# ARDUINO_MEGA2560_EXPANSION_BOARD.net
KiCad netlist of a schematic drawn in Altium Designer
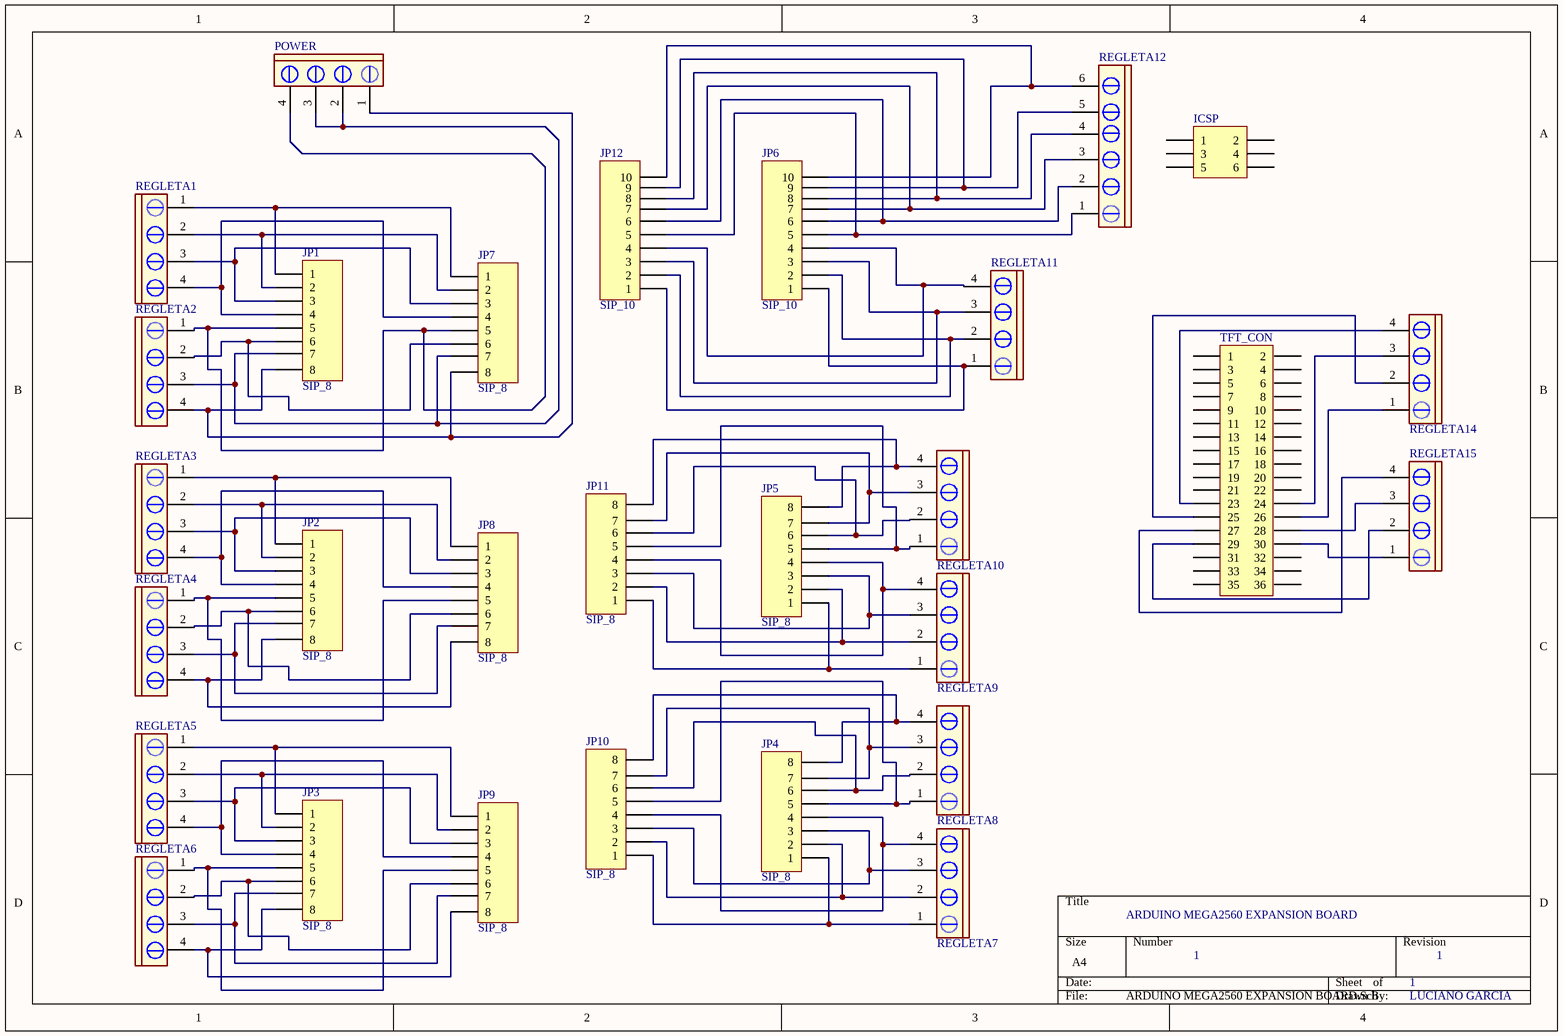
[diagram p0: ARDUINO MEGA2560 EXPANSION BOARD.SchDoc]

(export (version "E")
  (design (tool "Eeschema 10.0.6"))
  (components
    (comp (ref "ICSP")
      (value "SIP_2X3")
      (footprint "SIP_2X03")
      (libsource (lib "COMPONENTES") (part "SIP_2X3"))
    )
    (comp (ref "JP1") (value "SIP_8") (footprint "SIP_8") (libsource (lib "COMPONENTES") (part "SIP_8")))
    (comp (ref "JP2") (value "SIP_8") (footprint "SIP_8") (libsource (lib "COMPONENTES") (part "SIP_8")))
    (comp (ref "JP3") (value "SIP_8") (footprint "SIP_8") (libsource (lib "COMPONENTES") (part "SIP_8")))
    (comp (ref "JP4") (value "SIP_8") (footprint "SIP_8") (libsource (lib "") (part "SIP_8_1")))
    (comp (ref "JP5") (value "SIP_8") (footprint "SIP_8") (libsource (lib "") (part "SIP_8_1")))
    (comp (ref "JP6") (value "SIP_10") (footprint "SIP_10") (libsource (lib "COMPONENTES") (part "SIP_10")))
    (comp (ref "JP7") (value "SIP_8") (footprint "SIP_8") (libsource (lib "COMPONENTES") (part "SIP_8")))
    (comp (ref "JP8") (value "SIP_8") (footprint "SIP_8") (libsource (lib "COMPONENTES") (part "SIP_8")))
    (comp (ref "JP9") (value "SIP_8") (footprint "SIP_8") (libsource (lib "COMPONENTES") (part "SIP_8")))
    (comp (ref "JP10") (value "SIP_8") (footprint "SIP_8") (libsource (lib "") (part "SIP_8_1")))
    (comp (ref "JP11") (value "SIP_8") (footprint "SIP_8") (libsource (lib "") (part "SIP_8_1")))
    (comp (ref "JP12") (value "SIP_10") (footprint "SIP_10") (libsource (lib "COMPONENTES") (part "SIP_10")))
    (comp (ref "POWER") (value "REGLETA_4") (footprint "REGLETA_4") (libsource (lib "") (part "REGLETA_4_2")))
    (comp (ref "REGLETA1")
      (value "REGLETA_4")
      (footprint "REGLETA_4")
      (libsource (lib "COMPONENTES") (part "REGLETA_4"))
    )
    (comp (ref "REGLETA2")
      (value "REGLETA_4")
      (footprint "REGLETA_4")
      (libsource (lib "COMPONENTES") (part "REGLETA_4"))
    )
    (comp (ref "REGLETA3")
      (value "REGLETA_4")
      (footprint "REGLETA_4")
      (libsource (lib "COMPONENTES") (part "REGLETA_4"))
    )
    (comp (ref "REGLETA4")
      (value "REGLETA_4")
      (footprint "REGLETA_4")
      (libsource (lib "COMPONENTES") (part "REGLETA_4"))
    )
    (comp (ref "REGLETA5")
      (value "REGLETA_4")
      (footprint "REGLETA_4")
      (libsource (lib "COMPONENTES") (part "REGLETA_4"))
    )
    (comp (ref "REGLETA6")
      (value "REGLETA_4")
      (footprint "REGLETA_4")
      (libsource (lib "COMPONENTES") (part "REGLETA_4"))
    )
    (comp (ref "REGLETA7")
      (value "REGLETA_4")
      (footprint "REGLETA_4")
      (libsource (lib "") (part "REGLETA_4_1"))
    )
    (comp (ref "REGLETA8")
      (value "REGLETA_4")
      (footprint "REGLETA_4")
      (libsource (lib "") (part "REGLETA_4_1"))
    )
    (comp (ref "REGLETA9")
      (value "REGLETA_4")
      (footprint "REGLETA_4")
      (libsource (lib "") (part "REGLETA_4_1"))
    )
    (comp (ref "REGLETA10")
      (value "REGLETA_4")
      (footprint "REGLETA_4")
      (libsource (lib "") (part "REGLETA_4_1"))
    )
    (comp (ref "REGLETA11")
      (value "REGLETA_4")
      (footprint "REGLETA_4")
      (libsource (lib "") (part "REGLETA_4_1"))
    )
    (comp (ref "REGLETA12")
      (value "REGLETA_6")
      (footprint "REGLETA_6")
      (libsource (lib "COMPONENTES") (part "REGLETA_6"))
    )
    (comp (ref "REGLETA14")
      (value "REGLETA_4")
      (footprint "REGLETA_4")
      (libsource (lib "") (part "REGLETA_4_1"))
    )
    (comp (ref "REGLETA15")
      (value "REGLETA_4")
      (footprint "REGLETA_4")
      (libsource (lib "") (part "REGLETA_4_1"))
    )
    (comp (ref "TFT_CON")
      (value "SIP_2X18")
      (footprint "SIP_2X18")
      (libsource (lib "COMPONENTES") (part "SIP_2X18"))
    )
  )
  (nets
    (net (code "1") (name "Net-(JP1-Pad1)") (class "Default")
      (node (ref "JP1") (pin "1") (pinfunction "1_1") (pintype "passive"))
      (node (ref "JP7") (pin "1") (pinfunction "1_1") (pintype "passive"))
      (node (ref "REGLETA1") (pin "1") (pinfunction "1_1") (pintype "passive"))
    )
    (net (code "2") (name "Net-(JP1-Pad2)") (class "Default")
      (node (ref "JP1") (pin "2") (pinfunction "2_2") (pintype "passive"))
      (node (ref "JP7") (pin "2") (pinfunction "2_2") (pintype "passive"))
      (node (ref "REGLETA1") (pin "2") (pinfunction "2_2") (pintype "passive"))
    )
    (net (code "3") (name "Net-(JP1-Pad3)") (class "Default")
      (node (ref "JP1") (pin "3") (pinfunction "3_3") (pintype "passive"))
      (node (ref "JP7") (pin "3") (pinfunction "3_3") (pintype "passive"))
      (node (ref "REGLETA1") (pin "3") (pinfunction "3_3") (pintype "passive"))
    )
    (net (code "4") (name "Net-(JP1-Pad4)") (class "Default")
      (node (ref "JP1") (pin "4") (pinfunction "4_4") (pintype "passive"))
      (node (ref "JP7") (pin "4") (pinfunction "4_4") (pintype "passive"))
      (node (ref "REGLETA1") (pin "4") (pinfunction "4_4") (pintype "passive"))
    )
    (net (code "5") (name "Net-(JP1-Pad5)") (class "Default")
      (node (ref "JP1") (pin "5") (pinfunction "5_5") (pintype "passive"))
      (node (ref "JP7") (pin "5") (pinfunction "5_5") (pintype "passive"))
      (node (ref "POWER") (pin "4") (pinfunction "4_4") (pintype "passive"))
      (node (ref "REGLETA2") (pin "1") (pinfunction "1_1") (pintype "passive"))
    )
    (net (code "6") (name "Net-(JP1-Pad6)") (class "Default")
      (node (ref "JP1") (pin "6") (pinfunction "6_6") (pintype "passive"))
      (node (ref "JP7") (pin "6") (pinfunction "6_6") (pintype "passive"))
      (node (ref "REGLETA2") (pin "2") (pinfunction "2_2") (pintype "passive"))
    )
    (net (code "7") (name "Net-(JP1-Pad7)") (class "Default")
      (node (ref "JP1") (pin "7") (pinfunction "7_7") (pintype "passive"))
      (node (ref "JP7") (pin "7") (pinfunction "7_7") (pintype "passive"))
      (node (ref "POWER") (pin "2") (pinfunction "2_2") (pintype "passive"))
      (node (ref "POWER") (pin "3") (pinfunction "3_3") (pintype "passive"))
      (node (ref "REGLETA2") (pin "3") (pinfunction "3_3") (pintype "passive"))
    )
    (net (code "8") (name "Net-(JP1-Pad8)") (class "Default")
      (node (ref "JP1") (pin "8") (pinfunction "8_8") (pintype "passive"))
      (node (ref "JP7") (pin "8") (pinfunction "8_8") (pintype "passive"))
      (node (ref "POWER") (pin "1") (pinfunction "1_1") (pintype "passive"))
      (node (ref "REGLETA2") (pin "4") (pinfunction "4_4") (pintype "passive"))
    )
    (net (code "9") (name "Net-(JP2-Pad1)") (class "Default")
      (node (ref "JP2") (pin "1") (pinfunction "1_1") (pintype "passive"))
      (node (ref "JP8") (pin "1") (pinfunction "1_1") (pintype "passive"))
      (node (ref "REGLETA3") (pin "1") (pinfunction "1_1") (pintype "passive"))
    )
    (net (code "10") (name "Net-(JP2-Pad2)") (class "Default")
      (node (ref "JP2") (pin "2") (pinfunction "2_2") (pintype "passive"))
      (node (ref "JP8") (pin "2") (pinfunction "2_2") (pintype "passive"))
      (node (ref "REGLETA3") (pin "2") (pinfunction "2_2") (pintype "passive"))
    )
    (net (code "11") (name "Net-(JP2-Pad3)") (class "Default")
      (node (ref "JP2") (pin "3") (pinfunction "3_3") (pintype "passive"))
      (node (ref "JP8") (pin "3") (pinfunction "3_3") (pintype "passive"))
      (node (ref "REGLETA3") (pin "3") (pinfunction "3_3") (pintype "passive"))
    )
    (net (code "12") (name "Net-(JP2-Pad4)") (class "Default")
      (node (ref "JP2") (pin "4") (pinfunction "4_4") (pintype "passive"))
      (node (ref "JP8") (pin "4") (pinfunction "4_4") (pintype "passive"))
      (node (ref "REGLETA3") (pin "4") (pinfunction "4_4") (pintype "passive"))
    )
    (net (code "13") (name "Net-(JP2-Pad5)") (class "Default")
      (node (ref "JP2") (pin "5") (pinfunction "5_5") (pintype "passive"))
      (node (ref "JP8") (pin "5") (pinfunction "5_5") (pintype "passive"))
      (node (ref "REGLETA4") (pin "1") (pinfunction "1_1") (pintype "passive"))
    )
    (net (code "14") (name "Net-(JP2-Pad6)") (class "Default")
      (node (ref "JP2") (pin "6") (pinfunction "6_6") (pintype "passive"))
      (node (ref "JP8") (pin "6") (pinfunction "6_6") (pintype "passive"))
      (node (ref "REGLETA4") (pin "2") (pinfunction "2_2") (pintype "passive"))
    )
    (net (code "15") (name "Net-(JP2-Pad7)") (class "Default")
      (node (ref "JP2") (pin "7") (pinfunction "7_7") (pintype "passive"))
      (node (ref "JP8") (pin "7") (pinfunction "7_7") (pintype "passive"))
      (node (ref "REGLETA4") (pin "3") (pinfunction "3_3") (pintype "passive"))
    )
    (net (code "16") (name "Net-(JP2-Pad8)") (class "Default")
      (node (ref "JP2") (pin "8") (pinfunction "8_8") (pintype "passive"))
      (node (ref "JP8") (pin "8") (pinfunction "8_8") (pintype "passive"))
      (node (ref "REGLETA4") (pin "4") (pinfunction "4_4") (pintype "passive"))
    )
    (net (code "17") (name "Net-(JP3-Pad1)") (class "Default")
      (node (ref "JP3") (pin "1") (pinfunction "1_1") (pintype "passive"))
      (node (ref "JP9") (pin "1") (pinfunction "1_1") (pintype "passive"))
      (node (ref "REGLETA5") (pin "1") (pinfunction "1_1") (pintype "passive"))
    )
    (net (code "18") (name "Net-(JP3-Pad2)") (class "Default")
      (node (ref "JP3") (pin "2") (pinfunction "2_2") (pintype "passive"))
      (node (ref "JP9") (pin "2") (pinfunction "2_2") (pintype "passive"))
      (node (ref "REGLETA5") (pin "2") (pinfunction "2_2") (pintype "passive"))
    )
    (net (code "19") (name "Net-(JP3-Pad3)") (class "Default")
      (node (ref "JP3") (pin "3") (pinfunction "3_3") (pintype "passive"))
      (node (ref "JP9") (pin "3") (pinfunction "3_3") (pintype "passive"))
      (node (ref "REGLETA5") (pin "3") (pinfunction "3_3") (pintype "passive"))
    )
    (net (code "20") (name "Net-(JP3-Pad4)") (class "Default")
      (node (ref "JP3") (pin "4") (pinfunction "4_4") (pintype "passive"))
      (node (ref "JP9") (pin "4") (pinfunction "4_4") (pintype "passive"))
      (node (ref "REGLETA5") (pin "4") (pinfunction "4_4") (pintype "passive"))
    )
    (net (code "21") (name "Net-(JP3-Pad5)") (class "Default")
      (node (ref "JP3") (pin "5") (pinfunction "5_5") (pintype "passive"))
      (node (ref "JP9") (pin "5") (pinfunction "5_5") (pintype "passive"))
      (node (ref "REGLETA6") (pin "1") (pinfunction "1_1") (pintype "passive"))
    )
    (net (code "22") (name "Net-(JP3-Pad6)") (class "Default")
      (node (ref "JP3") (pin "6") (pinfunction "6_6") (pintype "passive"))
      (node (ref "JP9") (pin "6") (pinfunction "6_6") (pintype "passive"))
      (node (ref "REGLETA6") (pin "2") (pinfunction "2_2") (pintype "passive"))
    )
    (net (code "23") (name "Net-(JP3-Pad7)") (class "Default")
      (node (ref "JP3") (pin "7") (pinfunction "7_7") (pintype "passive"))
      (node (ref "JP9") (pin "7") (pinfunction "7_7") (pintype "passive"))
      (node (ref "REGLETA6") (pin "3") (pinfunction "3_3") (pintype "passive"))
    )
    (net (code "24") (name "Net-(JP3-Pad8)") (class "Default")
      (node (ref "JP3") (pin "8") (pinfunction "8_8") (pintype "passive"))
      (node (ref "JP9") (pin "8") (pinfunction "8_8") (pintype "passive"))
      (node (ref "REGLETA6") (pin "4") (pinfunction "4_4") (pintype "passive"))
    )
    (net (code "25") (name "Net-(JP10-Pad1)") (class "Default")
      (node (ref "JP10") (pin "1") (pinfunction "1_1") (pintype "passive"))
      (node (ref "JP4") (pin "1") (pinfunction "1_1") (pintype "passive"))
      (node (ref "REGLETA7") (pin "1") (pinfunction "1_1") (pintype "passive"))
    )
    (net (code "26") (name "Net-(JP10-Pad2)") (class "Default")
      (node (ref "JP10") (pin "2") (pinfunction "2_2") (pintype "passive"))
      (node (ref "JP4") (pin "2") (pinfunction "2_2") (pintype "passive"))
      (node (ref "REGLETA7") (pin "2") (pinfunction "2_2") (pintype "passive"))
    )
    (net (code "27") (name "Net-(JP10-Pad3)") (class "Default")
      (node (ref "JP10") (pin "3") (pinfunction "3_3") (pintype "passive"))
      (node (ref "JP4") (pin "3") (pinfunction "3_3") (pintype "passive"))
      (node (ref "REGLETA7") (pin "3") (pinfunction "3_3") (pintype "passive"))
    )
    (net (code "28") (name "Net-(JP10-Pad4)") (class "Default")
      (node (ref "JP10") (pin "4") (pinfunction "4_4") (pintype "passive"))
      (node (ref "JP4") (pin "4") (pinfunction "4_4") (pintype "passive"))
      (node (ref "REGLETA7") (pin "4") (pinfunction "4_4") (pintype "passive"))
    )
    (net (code "29") (name "Net-(JP10-Pad5)") (class "Default")
      (node (ref "JP10") (pin "5") (pinfunction "5_5") (pintype "passive"))
      (node (ref "JP4") (pin "5") (pinfunction "5_5") (pintype "passive"))
      (node (ref "REGLETA8") (pin "1") (pinfunction "1_1") (pintype "passive"))
    )
    (net (code "30") (name "Net-(JP10-Pad6)") (class "Default")
      (node (ref "JP10") (pin "6") (pinfunction "6_6") (pintype "passive"))
      (node (ref "JP4") (pin "6") (pinfunction "6_6") (pintype "passive"))
      (node (ref "REGLETA8") (pin "2") (pinfunction "2_2") (pintype "passive"))
    )
    (net (code "31") (name "Net-(JP10-Pad7)") (class "Default")
      (node (ref "JP10") (pin "7") (pinfunction "7_7") (pintype "passive"))
      (node (ref "JP4") (pin "7") (pinfunction "7_7") (pintype "passive"))
      (node (ref "REGLETA8") (pin "3") (pinfunction "3_3") (pintype "passive"))
    )
    (net (code "32") (name "Net-(JP10-Pad8)") (class "Default")
      (node (ref "JP10") (pin "8") (pinfunction "8_8") (pintype "passive"))
      (node (ref "JP4") (pin "8") (pinfunction "8_8") (pintype "passive"))
      (node (ref "REGLETA8") (pin "4") (pinfunction "4_4") (pintype "passive"))
    )
    (net (code "33") (name "Net-(JP11-Pad1)") (class "Default")
      (node (ref "JP11") (pin "1") (pinfunction "1_1") (pintype "passive"))
      (node (ref "JP5") (pin "1") (pinfunction "1_1") (pintype "passive"))
      (node (ref "REGLETA9") (pin "1") (pinfunction "1_1") (pintype "passive"))
    )
    (net (code "34") (name "Net-(JP11-Pad2)") (class "Default")
      (node (ref "JP11") (pin "2") (pinfunction "2_2") (pintype "passive"))
      (node (ref "JP5") (pin "2") (pinfunction "2_2") (pintype "passive"))
      (node (ref "REGLETA9") (pin "2") (pinfunction "2_2") (pintype "passive"))
    )
    (net (code "35") (name "Net-(JP11-Pad3)") (class "Default")
      (node (ref "JP11") (pin "3") (pinfunction "3_3") (pintype "passive"))
      (node (ref "JP5") (pin "3") (pinfunction "3_3") (pintype "passive"))
      (node (ref "REGLETA9") (pin "3") (pinfunction "3_3") (pintype "passive"))
    )
    (net (code "36") (name "Net-(JP11-Pad4)") (class "Default")
      (node (ref "JP11") (pin "4") (pinfunction "4_4") (pintype "passive"))
      (node (ref "JP5") (pin "4") (pinfunction "4_4") (pintype "passive"))
      (node (ref "REGLETA9") (pin "4") (pinfunction "4_4") (pintype "passive"))
    )
    (net (code "37") (name "Net-(JP11-Pad5)") (class "Default")
      (node (ref "JP11") (pin "5") (pinfunction "5_5") (pintype "passive"))
      (node (ref "JP5") (pin "5") (pinfunction "5_5") (pintype "passive"))
      (node (ref "REGLETA10") (pin "1") (pinfunction "1_1") (pintype "passive"))
    )
    (net (code "38") (name "Net-(JP11-Pad6)") (class "Default")
      (node (ref "JP11") (pin "6") (pinfunction "6_6") (pintype "passive"))
      (node (ref "JP5") (pin "6") (pinfunction "6_6") (pintype "passive"))
      (node (ref "REGLETA10") (pin "2") (pinfunction "2_2") (pintype "passive"))
    )
    (net (code "39") (name "Net-(JP11-Pad7)") (class "Default")
      (node (ref "JP11") (pin "7") (pinfunction "7_7") (pintype "passive"))
      (node (ref "JP5") (pin "7") (pinfunction "7_7") (pintype "passive"))
      (node (ref "REGLETA10") (pin "3") (pinfunction "3_3") (pintype "passive"))
    )
    (net (code "40") (name "Net-(JP11-Pad8)") (class "Default")
      (node (ref "JP11") (pin "8") (pinfunction "8_8") (pintype "passive"))
      (node (ref "JP5") (pin "8") (pinfunction "8_8") (pintype "passive"))
      (node (ref "REGLETA10") (pin "4") (pinfunction "4_4") (pintype "passive"))
    )
    (net (code "41") (name "Net-(JP12-Pad1)") (class "Default")
      (node (ref "JP12") (pin "1") (pinfunction "1_1") (pintype "passive"))
      (node (ref "JP6") (pin "1") (pinfunction "1_1") (pintype "passive"))
      (node (ref "REGLETA11") (pin "1") (pinfunction "1_1") (pintype "passive"))
    )
    (net (code "42") (name "Net-(JP12-Pad2)") (class "Default")
      (node (ref "JP12") (pin "2") (pinfunction "2_2") (pintype "passive"))
      (node (ref "JP6") (pin "2") (pinfunction "2_2") (pintype "passive"))
      (node (ref "REGLETA11") (pin "2") (pinfunction "2_2") (pintype "passive"))
    )
    (net (code "43") (name "Net-(JP12-Pad3)") (class "Default")
      (node (ref "JP12") (pin "3") (pinfunction "3_3") (pintype "passive"))
      (node (ref "JP6") (pin "3") (pinfunction "3_3") (pintype "passive"))
      (node (ref "REGLETA11") (pin "3") (pinfunction "3_3") (pintype "passive"))
    )
    (net (code "44") (name "Net-(JP12-Pad4)") (class "Default")
      (node (ref "JP12") (pin "4") (pinfunction "4_4") (pintype "passive"))
      (node (ref "JP6") (pin "4") (pinfunction "4_4") (pintype "passive"))
      (node (ref "REGLETA11") (pin "4") (pinfunction "4_4") (pintype "passive"))
    )
    (net (code "45") (name "Net-(JP12-Pad5)") (class "Default")
      (node (ref "JP12") (pin "5") (pinfunction "5_5") (pintype "passive"))
      (node (ref "JP6") (pin "5") (pinfunction "5_5") (pintype "passive"))
      (node (ref "REGLETA12") (pin "1") (pinfunction "1_1") (pintype "passive"))
    )
    (net (code "46") (name "Net-(JP12-Pad6)") (class "Default")
      (node (ref "JP12") (pin "6") (pinfunction "6_6") (pintype "passive"))
      (node (ref "JP6") (pin "6") (pinfunction "6_6") (pintype "passive"))
      (node (ref "REGLETA12") (pin "2") (pinfunction "2_2") (pintype "passive"))
    )
    (net (code "47") (name "Net-(JP12-Pad7)") (class "Default")
      (node (ref "JP12") (pin "7") (pinfunction "7_7") (pintype "passive"))
      (node (ref "JP6") (pin "7") (pinfunction "7_7") (pintype "passive"))
      (node (ref "REGLETA12") (pin "3") (pinfunction "3_3") (pintype "passive"))
    )
    (net (code "48") (name "Net-(JP12-Pad8)") (class "Default")
      (node (ref "JP12") (pin "8") (pinfunction "8_8") (pintype "passive"))
      (node (ref "JP6") (pin "8") (pinfunction "8_8") (pintype "passive"))
      (node (ref "REGLETA12") (pin "4") (pinfunction "4_4") (pintype "passive"))
    )
    (net (code "49") (name "Net-(JP12-Pad9)") (class "Default")
      (node (ref "JP12") (pin "9") (pinfunction "9_9") (pintype "passive"))
      (node (ref "JP6") (pin "9") (pinfunction "9_9") (pintype "passive"))
      (node (ref "REGLETA12") (pin "5") (pinfunction "5_5") (pintype "passive"))
    )
    (net (code "50") (name "Net-(JP12-Pad10)") (class "Default")
      (node (ref "JP12") (pin "10") (pinfunction "10_10") (pintype "passive"))
      (node (ref "JP6") (pin "10") (pinfunction "10_10") (pintype "passive"))
      (node (ref "REGLETA12") (pin "6") (pinfunction "6_6") (pintype "passive"))
    )
    (net (code "51") (name "Net-(REGLETA14-Pad1)") (class "Default")
      (node (ref "REGLETA14") (pin "1") (pinfunction "1_1") (pintype "passive"))
      (node (ref "TFT_CON") (pin "26") (pinfunction "26_26") (pintype "passive"))
    )
    (net (code "52") (name "Net-(REGLETA14-Pad2)") (class "Default")
      (node (ref "REGLETA14") (pin "2") (pinfunction "2_2") (pintype "passive"))
      (node (ref "TFT_CON") (pin "25") (pinfunction "25_25") (pintype "passive"))
    )
    (net (code "53") (name "Net-(REGLETA14-Pad3)") (class "Default")
      (node (ref "REGLETA14") (pin "3") (pinfunction "3_3") (pintype "passive"))
      (node (ref "TFT_CON") (pin "24") (pinfunction "24_24") (pintype "passive"))
    )
    (net (code "54") (name "Net-(REGLETA14-Pad4)") (class "Default")
      (node (ref "REGLETA14") (pin "4") (pinfunction "4_4") (pintype "passive"))
      (node (ref "TFT_CON") (pin "23") (pinfunction "23_23") (pintype "passive"))
    )
    (net (code "55") (name "Net-(REGLETA15-Pad1)") (class "Default")
      (node (ref "REGLETA15") (pin "1") (pinfunction "1_1") (pintype "passive"))
      (node (ref "TFT_CON") (pin "30") (pinfunction "30_30") (pintype "passive"))
    )
    (net (code "56") (name "Net-(REGLETA15-Pad2)") (class "Default")
      (node (ref "REGLETA15") (pin "2") (pinfunction "2_2") (pintype "passive"))
      (node (ref "TFT_CON") (pin "29") (pinfunction "29_29") (pintype "passive"))
    )
    (net (code "57") (name "Net-(REGLETA15-Pad3)") (class "Default")
      (node (ref "REGLETA15") (pin "3") (pinfunction "3_3") (pintype "passive"))
      (node (ref "TFT_CON") (pin "28") (pinfunction "28_28") (pintype "passive"))
    )
    (net (code "58") (name "Net-(REGLETA15-Pad4)") (class "Default")
      (node (ref "REGLETA15") (pin "4") (pinfunction "4_4") (pintype "passive"))
      (node (ref "TFT_CON") (pin "27") (pinfunction "27_27") (pintype "passive"))
    )
    (net (code "59") (name "unconnected-(ICSP-Pad1)") (class "Default")
      (node (ref "ICSP") (pin "1") (pinfunction "1_1") (pintype "passive"))
    )
    (net (code "60") (name "unconnected-(ICSP-Pad2)") (class "Default")
      (node (ref "ICSP") (pin "2") (pinfunction "2_2") (pintype "passive"))
    )
    (net (code "61") (name "unconnected-(ICSP-Pad3)") (class "Default")
      (node (ref "ICSP") (pin "3") (pinfunction "3_3") (pintype "passive"))
    )
    (net (code "62") (name "unconnected-(ICSP-Pad4)") (class "Default")
      (node (ref "ICSP") (pin "4") (pinfunction "4_4") (pintype "passive"))
    )
    (net (code "63") (name "unconnected-(ICSP-Pad5)") (class "Default")
      (node (ref "ICSP") (pin "5") (pinfunction "5_5") (pintype "passive"))
    )
    (net (code "64") (name "unconnected-(ICSP-Pad6)") (class "Default")
      (node (ref "ICSP") (pin "6") (pinfunction "6_6") (pintype "passive"))
    )
    (net (code "65") (name "unconnected-(TFT_CON-Pad1)") (class "Default")
      (node (ref "TFT_CON") (pin "1") (pinfunction "1_1") (pintype "passive"))
    )
    (net (code "66") (name "unconnected-(TFT_CON-Pad2)") (class "Default")
      (node (ref "TFT_CON") (pin "2") (pinfunction "2_2") (pintype "passive"))
    )
    (net (code "67") (name "unconnected-(TFT_CON-Pad3)") (class "Default")
      (node (ref "TFT_CON") (pin "3") (pinfunction "3_3") (pintype "passive"))
    )
    (net (code "68") (name "unconnected-(TFT_CON-Pad4)") (class "Default")
      (node (ref "TFT_CON") (pin "4") (pinfunction "4_4") (pintype "passive"))
    )
    (net (code "69") (name "unconnected-(TFT_CON-Pad5)") (class "Default")
      (node (ref "TFT_CON") (pin "5") (pinfunction "5_5") (pintype "passive"))
    )
    (net (code "70") (name "unconnected-(TFT_CON-Pad6)") (class "Default")
      (node (ref "TFT_CON") (pin "6") (pinfunction "6_6") (pintype "passive"))
    )
    (net (code "71") (name "unconnected-(TFT_CON-Pad7)") (class "Default")
      (node (ref "TFT_CON") (pin "7") (pinfunction "7_7") (pintype "passive"))
    )
    (net (code "72") (name "unconnected-(TFT_CON-Pad8)") (class "Default")
      (node (ref "TFT_CON") (pin "8") (pinfunction "8_8") (pintype "passive"))
    )
    (net (code "73") (name "unconnected-(TFT_CON-Pad9)") (class "Default")
      (node (ref "TFT_CON") (pin "9") (pinfunction "9_9") (pintype "passive"))
    )
    (net (code "74") (name "unconnected-(TFT_CON-Pad10)") (class "Default")
      (node (ref "TFT_CON") (pin "10") (pinfunction "10_10") (pintype "passive"))
    )
    (net (code "75") (name "unconnected-(TFT_CON-Pad11)") (class "Default")
      (node (ref "TFT_CON") (pin "11") (pinfunction "11_11") (pintype "passive"))
    )
    (net (code "76") (name "unconnected-(TFT_CON-Pad12)") (class "Default")
      (node (ref "TFT_CON") (pin "12") (pinfunction "12_12") (pintype "passive"))
    )
    (net (code "77") (name "unconnected-(TFT_CON-Pad13)") (class "Default")
      (node (ref "TFT_CON") (pin "13") (pinfunction "13_13") (pintype "passive"))
    )
    (net (code "78") (name "unconnected-(TFT_CON-Pad14)") (class "Default")
      (node (ref "TFT_CON") (pin "14") (pinfunction "14_14") (pintype "passive"))
    )
    (net (code "79") (name "unconnected-(TFT_CON-Pad15)") (class "Default")
      (node (ref "TFT_CON") (pin "15") (pinfunction "15_15") (pintype "passive"))
    )
    (net (code "80") (name "unconnected-(TFT_CON-Pad16)") (class "Default")
      (node (ref "TFT_CON") (pin "16") (pinfunction "16_16") (pintype "passive"))
    )
    (net (code "81") (name "unconnected-(TFT_CON-Pad17)") (class "Default")
      (node (ref "TFT_CON") (pin "17") (pinfunction "17_17") (pintype "passive"))
    )
    (net (code "82") (name "unconnected-(TFT_CON-Pad18)") (class "Default")
      (node (ref "TFT_CON") (pin "18") (pinfunction "18_18") (pintype "passive"))
    )
    (net (code "83") (name "unconnected-(TFT_CON-Pad19)") (class "Default")
      (node (ref "TFT_CON") (pin "19") (pinfunction "19_19") (pintype "passive"))
    )
    (net (code "84") (name "unconnected-(TFT_CON-Pad20)") (class "Default")
      (node (ref "TFT_CON") (pin "20") (pinfunction "20_20") (pintype "passive"))
    )
    (net (code "85") (name "unconnected-(TFT_CON-Pad21)") (class "Default")
      (node (ref "TFT_CON") (pin "21") (pinfunction "21_21") (pintype "passive"))
    )
    (net (code "86") (name "unconnected-(TFT_CON-Pad22)") (class "Default")
      (node (ref "TFT_CON") (pin "22") (pinfunction "22_22") (pintype "passive"))
    )
    (net (code "87") (name "unconnected-(TFT_CON-Pad31)") (class "Default")
      (node (ref "TFT_CON") (pin "31") (pinfunction "31_31") (pintype "passive"))
    )
    (net (code "88") (name "unconnected-(TFT_CON-Pad32)") (class "Default")
      (node (ref "TFT_CON") (pin "32") (pinfunction "32_32") (pintype "passive"))
    )
    (net (code "89") (name "unconnected-(TFT_CON-Pad33)") (class "Default")
      (node (ref "TFT_CON") (pin "33") (pinfunction "33_33") (pintype "passive"))
    )
    (net (code "90") (name "unconnected-(TFT_CON-Pad34)") (class "Default")
      (node (ref "TFT_CON") (pin "34") (pinfunction "34_34") (pintype "passive"))
    )
    (net (code "91") (name "unconnected-(TFT_CON-Pad35)") (class "Default")
      (node (ref "TFT_CON") (pin "35") (pinfunction "35_35") (pintype "passive"))
    )
    (net (code "92") (name "unconnected-(TFT_CON-Pad36)") (class "Default")
      (node (ref "TFT_CON") (pin "36") (pinfunction "36_36") (pintype "passive"))
    )
  )
)
